# Knight_Rider.net
KiCad netlist of a schematic drawn in EasyEDA Pro
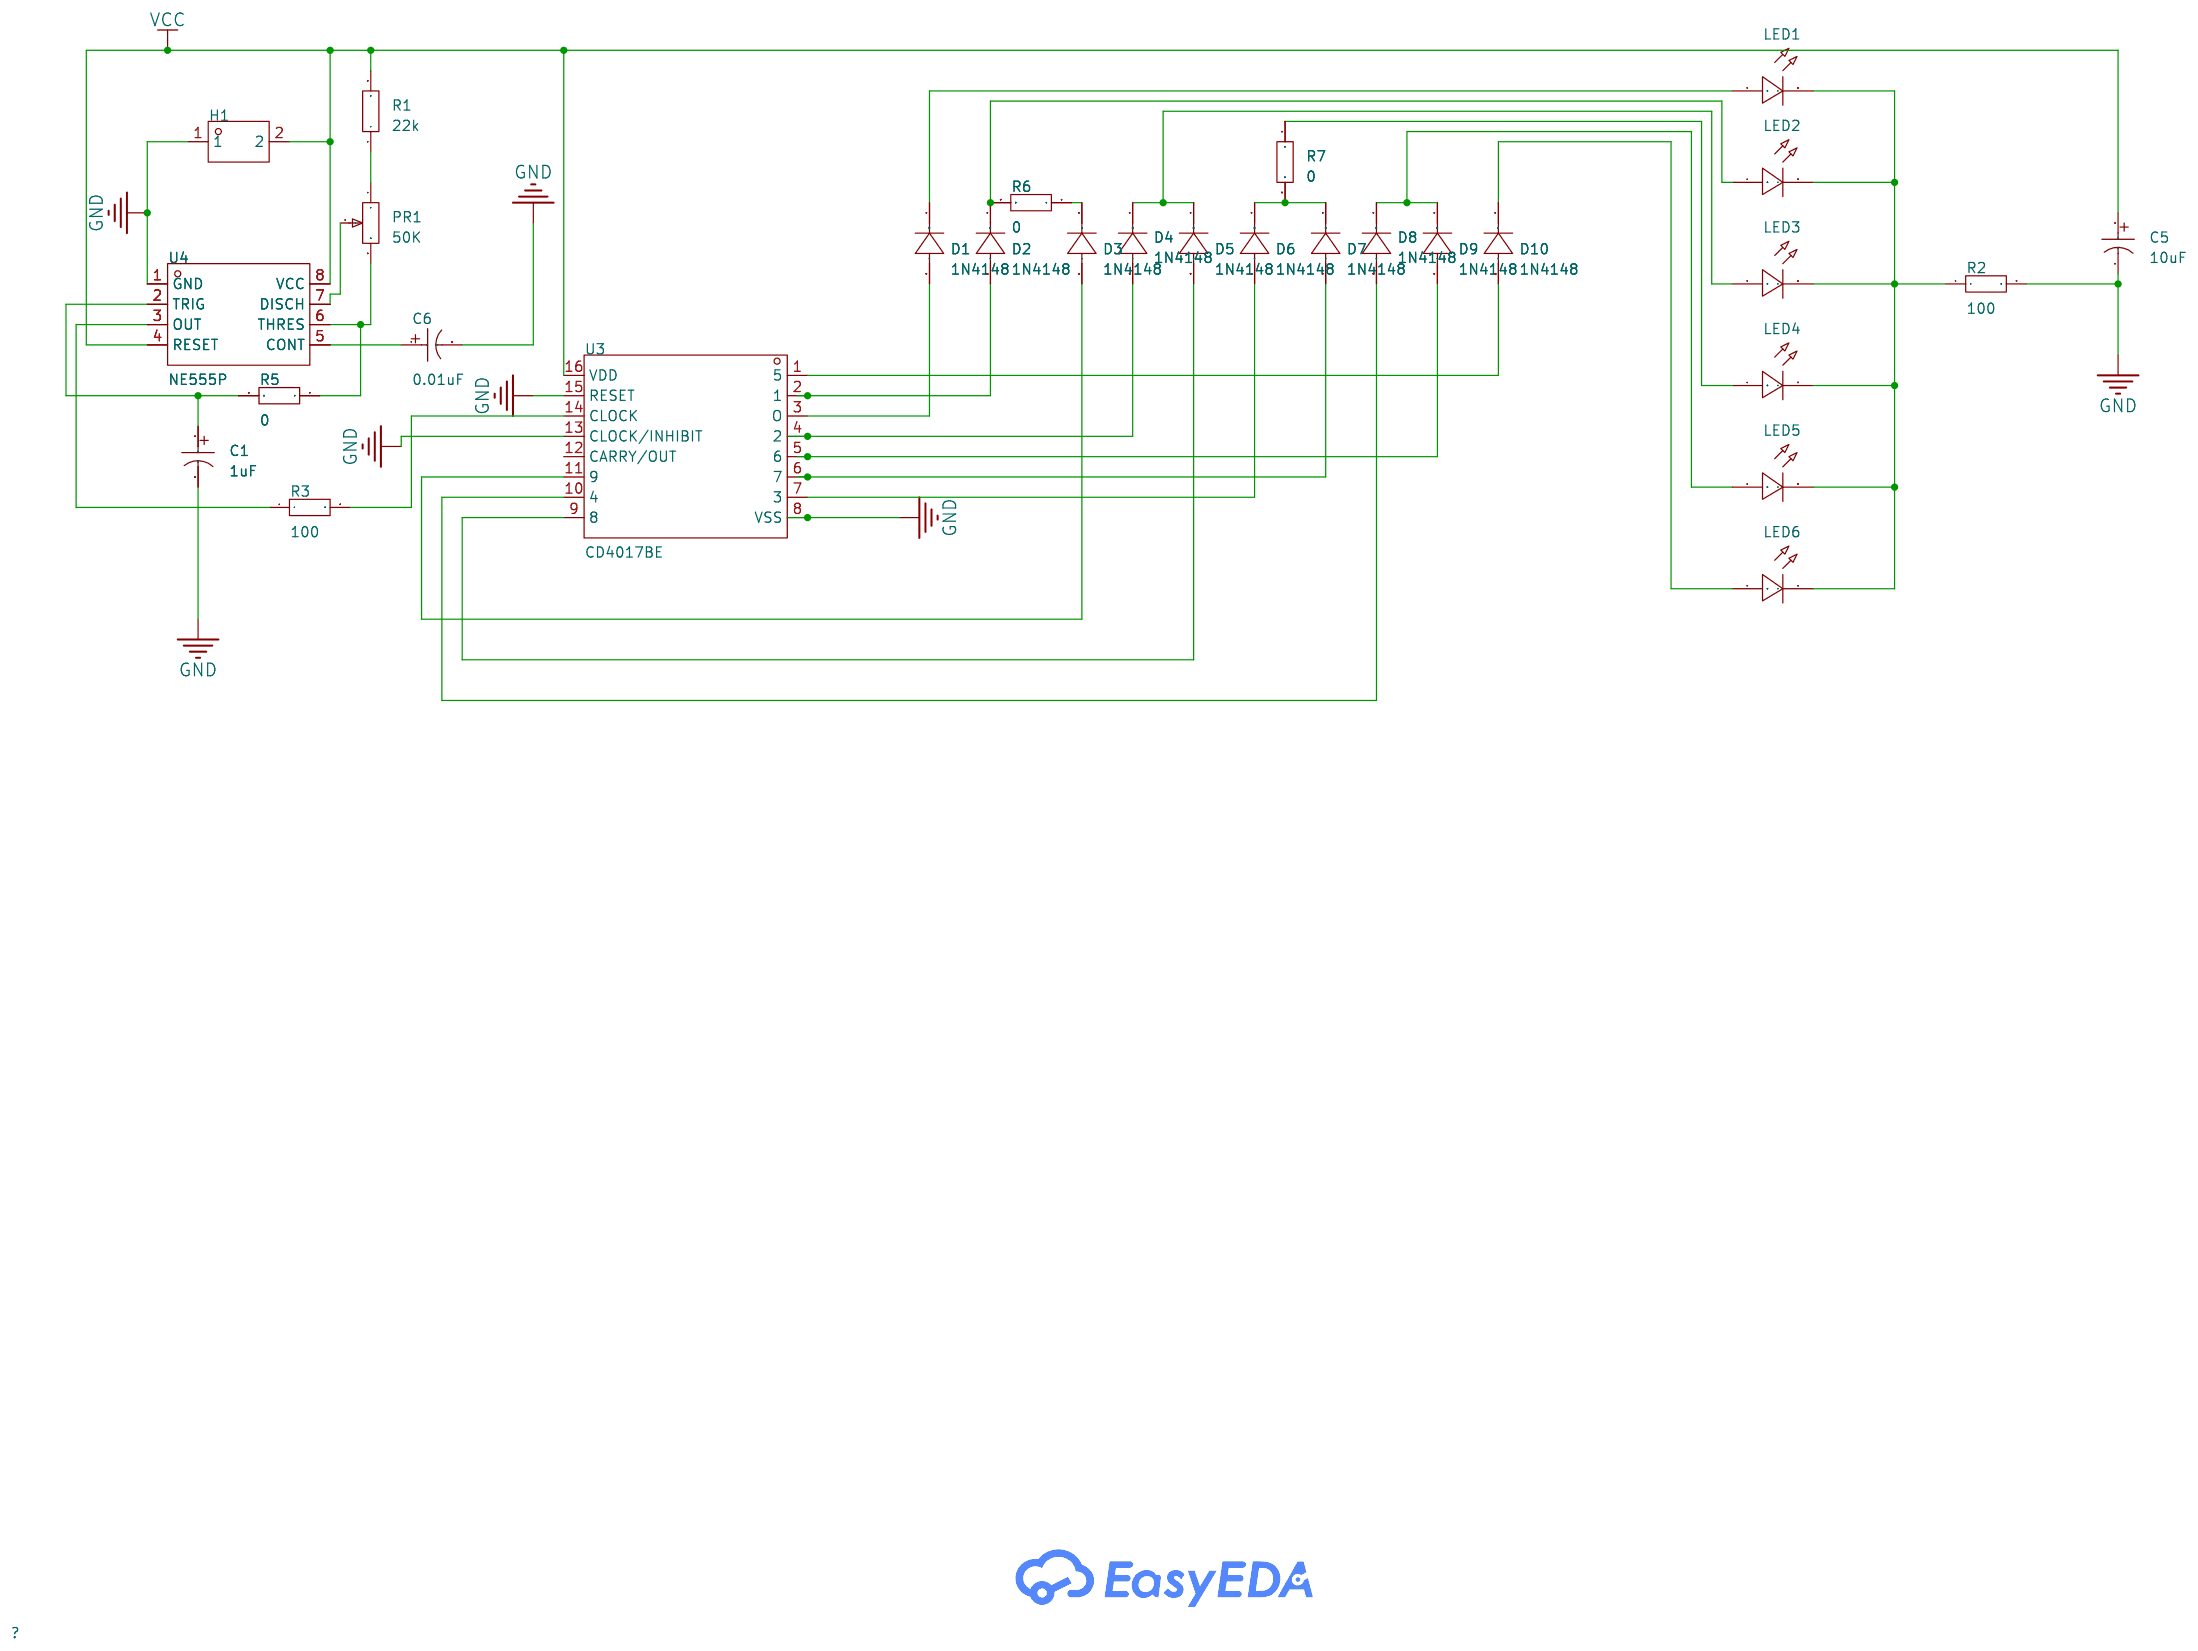
[diagram p0: schematic sheet]

(export (version "E")
  (design (tool "Eeschema 10.0.6"))
  (components
    (comp (ref "C1")
      (value "1uF")
      (footprint "easyedapro:CAP-TH_BD6.3-P2.50-D1.0-FD")
      (fields
        (field (name "Manufacturer Part") "KS227M016E07RR0VH2FP0")
        (field (name "Manufacturer") "Chengx(承兴)")
      )
      (libsource (lib "easyedapro") (part "220uF 16V 6.3*7"))
    )
    (comp (ref "C5")
      (value "10uF")
      (footprint "easyedapro:CAP-TH_BD6.3-P2.50-D1.0-FD")
      (fields
        (field (name "Manufacturer Part") "KS227M016E07RR0VH2FP0")
        (field (name "Manufacturer") "Chengx(承兴)")
      )
      (libsource (lib "easyedapro") (part "220uF 16V 6.3*7"))
    )
    (comp (ref "C6")
      (value "0.01uF")
      (footprint "easyedapro:CAP-TH_BD6.3-P2.50-D1.0-FD")
      (fields
        (field (name "Manufacturer Part") "KS227M016E07RR0VH2FP0")
        (field (name "Manufacturer") "Chengx(承兴)")
      )
      (libsource (lib "easyedapro") (part "220uF 16V 6.3*7"))
    )
    (comp (ref "D1")
      (value "1N4148")
      (footprint "easyedapro:DO-35_BD1.7-L3.6-P10.00-D0.5-RD")
      (fields (field (name "Manufacturer") "DIOTEC(德欧泰克)"))
      (libsource (lib "easyedapro") (part "1N4148_C22434654"))
    )
    (comp (ref "D2")
      (value "1N4148")
      (footprint "easyedapro:DO-35_BD1.7-L3.6-P10.00-D0.5-RD")
      (fields (field (name "Manufacturer") "DIOTEC(德欧泰克)"))
      (libsource (lib "easyedapro") (part "1N4148_C22434654"))
    )
    (comp (ref "D3")
      (value "1N4148")
      (footprint "easyedapro:DO-35_BD1.7-L3.6-P10.00-D0.5-RD")
      (fields (field (name "Manufacturer") "DIOTEC(德欧泰克)"))
      (libsource (lib "easyedapro") (part "1N4148_C22434654"))
    )
    (comp (ref "D4")
      (value "1N4148")
      (footprint "easyedapro:DO-35_BD1.7-L3.6-P10.00-D0.5-RD")
      (fields (field (name "Manufacturer") "DIOTEC(德欧泰克)"))
      (libsource (lib "easyedapro") (part "1N4148_C22434654"))
    )
    (comp (ref "D5")
      (value "1N4148")
      (footprint "easyedapro:DO-35_BD1.7-L3.6-P10.00-D0.5-RD")
      (fields (field (name "Manufacturer") "DIOTEC(德欧泰克)"))
      (libsource (lib "easyedapro") (part "1N4148_C22434654"))
    )
    (comp (ref "D6")
      (value "1N4148")
      (footprint "easyedapro:DO-35_BD1.7-L3.6-P10.00-D0.5-RD")
      (fields (field (name "Manufacturer") "DIOTEC(德欧泰克)"))
      (libsource (lib "easyedapro") (part "1N4148_C22434654"))
    )
    (comp (ref "D7")
      (value "1N4148")
      (footprint "easyedapro:DO-35_BD1.7-L3.6-P10.00-D0.5-RD")
      (fields (field (name "Manufacturer") "DIOTEC(德欧泰克)"))
      (libsource (lib "easyedapro") (part "1N4148_C22434654"))
    )
    (comp (ref "D8")
      (value "1N4148")
      (footprint "easyedapro:DO-35_BD1.7-L3.6-P10.00-D0.5-RD")
      (fields (field (name "Manufacturer") "DIOTEC(德欧泰克)"))
      (libsource (lib "easyedapro") (part "1N4148_C22434654"))
    )
    (comp (ref "D9")
      (value "1N4148")
      (footprint "easyedapro:DO-35_BD1.7-L3.6-P10.00-D0.5-RD")
      (fields (field (name "Manufacturer") "DIOTEC(德欧泰克)"))
      (libsource (lib "easyedapro") (part "1N4148_C22434654"))
    )
    (comp (ref "D10")
      (value "1N4148")
      (footprint "easyedapro:DO-35_BD1.7-L3.6-P10.00-D0.5-RD")
      (fields (field (name "Manufacturer") "DIOTEC(德欧泰克)"))
      (libsource (lib "easyedapro") (part "1N4148_C22434654"))
    )
    (comp (ref "H1")
      (value "~")
      (footprint "easyedapro:HDR-TH_2P-P2.54-V-M-2")
      (libsource (lib "easyedapro") (part "HDR-M-2.54_2x1"))
    )
    (comp (ref "LED1")
      (value "~")
      (footprint "easyedapro:LED-TH_BD3.0-P2.54-FD")
      (libsource (lib "easyedapro") (part "LED_TH-R"))
    )
    (comp (ref "LED2")
      (value "~")
      (footprint "easyedapro:LED-TH_BD3.0-P2.54-FD")
      (libsource (lib "easyedapro") (part "LED_TH-R"))
    )
    (comp (ref "LED3")
      (value "~")
      (footprint "easyedapro:LED-TH_BD3.0-P2.54-FD")
      (libsource (lib "easyedapro") (part "LED_TH-R"))
    )
    (comp (ref "LED4")
      (value "~")
      (footprint "easyedapro:LED-TH_BD3.0-P2.54-FD")
      (libsource (lib "easyedapro") (part "LED_TH-R"))
    )
    (comp (ref "LED5")
      (value "~")
      (footprint "easyedapro:LED-TH_BD3.0-P2.54-FD")
      (libsource (lib "easyedapro") (part "LED_TH-R"))
    )
    (comp (ref "LED6")
      (value "~")
      (footprint "easyedapro:LED-TH_BD3.0-P2.54-FD")
      (libsource (lib "easyedapro") (part "LED_TH-R"))
    )
    (comp (ref "PR1")
      (value "50K")
      (footprint "easyedapro:RES-ADJ-TH_3P-L9.5-W9.5-P2.54-BR-BS")
      (libsource (lib "easyedapro") (part "3386P-1-103LF"))
    )
    (comp (ref "R1")
      (value "22k")
      (footprint "easyedapro:RES-TH_BD1.8-L3.2-P7.20-D0.4")
      (libsource (lib "easyedapro") (part "Res"))
    )
    (comp (ref "R2")
      (value "100")
      (footprint "easyedapro:RES-TH_BD1.8-L3.2-P7.20-D0.4")
      (libsource (lib "easyedapro") (part "Res"))
    )
    (comp (ref "R3")
      (value "100")
      (footprint "easyedapro:RES-TH_BD1.8-L3.2-P7.20-D0.4")
      (libsource (lib "easyedapro") (part "Res"))
    )
    (comp (ref "R5")
      (value "0")
      (footprint "easyedapro:RES-TH_BD1.8-L3.2-P7.20-D0.4")
      (libsource (lib "easyedapro") (part "Res"))
    )
    (comp (ref "R6")
      (value "0")
      (footprint "easyedapro:RES-TH_BD1.8-L3.2-P7.20-D0.4")
      (libsource (lib "easyedapro") (part "Res"))
    )
    (comp (ref "R7")
      (value "0")
      (footprint "easyedapro:RES-TH_BD1.8-L3.2-P7.20-D0.4")
      (libsource (lib "easyedapro") (part "Res"))
    )
    (comp (ref "U3")
      (value "CD4017BE")
      (footprint "easyedapro:DIP-16_16P-L20.2-W6.6-P2.54-LS7.6-BL")
      (fields (field (name "Manufacturer") "TI(德州仪器)"))
      (libsource (lib "easyedapro") (part "CD4017BE"))
    )
    (comp (ref "U4")
      (value "NE555P")
      (footprint "easyedapro:DIP-8_L9.8-W6.6-P2.54-LS7.6-BL")
      (fields (field (name "Manufacturer") "TI(德州仪器)"))
      (libsource (lib "easyedapro") (part "NE555P"))
    )
  )
  (nets
    (net (code "1") (name "GND") (class "Default")
      (node (ref "C1") (pin "2") (pinfunction "2_2") (pintype "input"))
      (node (ref "C5") (pin "2") (pinfunction "2_2") (pintype "input"))
      (node (ref "C6") (pin "2") (pinfunction "2_2") (pintype "input"))
      (node (ref "H1") (pin "1") (pinfunction "1_1") (pintype "input"))
      (node (ref "R2") (pin "2") (pinfunction "2_2") (pintype "input"))
      (node (ref "U3") (pin "13") (pinfunction "CLOCK/INHIBIT_13") (pintype "unspecified"))
      (node (ref "U3") (pin "15") (pinfunction "RESET_15") (pintype "unspecified"))
      (node (ref "U3") (pin "8") (pinfunction "VSS_8") (pintype "unspecified"))
      (node (ref "U4") (pin "1") (pinfunction "GND_1") (pintype "input"))
    )
    (net (code "2") (name "Net-(D1-A)") (class "Default")
      (node (ref "D1") (pin "2") (pinfunction "A_2") (pintype "unspecified"))
      (node (ref "U3") (pin "3") (pinfunction "O_3") (pintype "unspecified"))
    )
    (net (code "3") (name "Net-(D1-C)") (class "Default")
      (node (ref "D1") (pin "1") (pinfunction "C_1") (pintype "unspecified"))
      (node (ref "LED1") (pin "1") (pinfunction "C_1") (pintype "input"))
    )
    (net (code "4") (name "Net-(D2-A)") (class "Default")
      (node (ref "D2") (pin "2") (pinfunction "A_2") (pintype "unspecified"))
      (node (ref "U3") (pin "2") (pinfunction "1_2") (pintype "unspecified"))
    )
    (net (code "5") (name "Net-(D2-C)") (class "Default")
      (node (ref "D2") (pin "1") (pinfunction "C_1") (pintype "unspecified"))
      (node (ref "LED2") (pin "1") (pinfunction "C_1") (pintype "input"))
      (node (ref "R6") (pin "2") (pinfunction "2_2") (pintype "input"))
    )
    (net (code "6") (name "Net-(D3-A)") (class "Default")
      (node (ref "D3") (pin "2") (pinfunction "A_2") (pintype "unspecified"))
      (node (ref "U3") (pin "11") (pinfunction "9_11") (pintype "unspecified"))
    )
    (net (code "7") (name "Net-(D3-C)") (class "Default")
      (node (ref "D3") (pin "1") (pinfunction "C_1") (pintype "unspecified"))
      (node (ref "R6") (pin "1") (pinfunction "1_1") (pintype "input"))
    )
    (net (code "8") (name "Net-(D4-A)") (class "Default")
      (node (ref "D4") (pin "2") (pinfunction "A_2") (pintype "unspecified"))
      (node (ref "U3") (pin "4") (pinfunction "2_4") (pintype "unspecified"))
    )
    (net (code "9") (name "Net-(D4-C)") (class "Default")
      (node (ref "D4") (pin "1") (pinfunction "C_1") (pintype "unspecified"))
      (node (ref "D5") (pin "1") (pinfunction "C_1") (pintype "unspecified"))
      (node (ref "LED3") (pin "1") (pinfunction "C_1") (pintype "input"))
    )
    (net (code "10") (name "Net-(D5-A)") (class "Default")
      (node (ref "D5") (pin "2") (pinfunction "A_2") (pintype "unspecified"))
      (node (ref "U3") (pin "9") (pinfunction "8_9") (pintype "unspecified"))
    )
    (net (code "11") (name "Net-(D6-A)") (class "Default")
      (node (ref "D6") (pin "2") (pinfunction "A_2") (pintype "unspecified"))
      (node (ref "U3") (pin "7") (pinfunction "3_7") (pintype "unspecified"))
    )
    (net (code "12") (name "Net-(D6-C)") (class "Default")
      (node (ref "D6") (pin "1") (pinfunction "C_1") (pintype "unspecified"))
      (node (ref "D7") (pin "1") (pinfunction "C_1") (pintype "unspecified"))
      (node (ref "R7") (pin "2") (pinfunction "2_2") (pintype "input"))
    )
    (net (code "13") (name "Net-(D7-A)") (class "Default")
      (node (ref "D7") (pin "2") (pinfunction "A_2") (pintype "unspecified"))
      (node (ref "U3") (pin "6") (pinfunction "7_6") (pintype "unspecified"))
    )
    (net (code "14") (name "Net-(D8-A)") (class "Default")
      (node (ref "D8") (pin "2") (pinfunction "A_2") (pintype "unspecified"))
      (node (ref "U3") (pin "10") (pinfunction "4_10") (pintype "unspecified"))
    )
    (net (code "15") (name "Net-(D8-C)") (class "Default")
      (node (ref "D8") (pin "1") (pinfunction "C_1") (pintype "unspecified"))
      (node (ref "D9") (pin "1") (pinfunction "C_1") (pintype "unspecified"))
      (node (ref "LED5") (pin "1") (pinfunction "C_1") (pintype "input"))
    )
    (net (code "16") (name "Net-(D9-A)") (class "Default")
      (node (ref "D9") (pin "2") (pinfunction "A_2") (pintype "unspecified"))
      (node (ref "U3") (pin "5") (pinfunction "6_5") (pintype "unspecified"))
    )
    (net (code "17") (name "Net-(D10-A)") (class "Default")
      (node (ref "D10") (pin "2") (pinfunction "A_2") (pintype "unspecified"))
      (node (ref "U3") (pin "1") (pinfunction "5_1") (pintype "unspecified"))
    )
    (net (code "18") (name "Net-(D10-C)") (class "Default")
      (node (ref "D10") (pin "1") (pinfunction "C_1") (pintype "unspecified"))
      (node (ref "LED6") (pin "1") (pinfunction "C_1") (pintype "input"))
    )
    (net (code "19") (name "Net-(LED1-A)") (class "Default")
      (node (ref "LED1") (pin "2") (pinfunction "A_2") (pintype "input"))
      (node (ref "LED2") (pin "2") (pinfunction "A_2") (pintype "input"))
      (node (ref "LED3") (pin "2") (pinfunction "A_2") (pintype "input"))
      (node (ref "LED4") (pin "2") (pinfunction "A_2") (pintype "input"))
      (node (ref "LED5") (pin "2") (pinfunction "A_2") (pintype "input"))
      (node (ref "LED6") (pin "2") (pinfunction "A_2") (pintype "input"))
      (node (ref "R2") (pin "1") (pinfunction "1_1") (pintype "input"))
    )
    (net (code "20") (name "Net-(LED4-C)") (class "Default")
      (node (ref "LED4") (pin "1") (pinfunction "C_1") (pintype "input"))
      (node (ref "R7") (pin "1") (pinfunction "1_1") (pintype "input"))
    )
    (net (code "21") (name "Net-(PR1-Pad1)") (class "Default")
      (node (ref "PR1") (pin "1") (pinfunction "1_1") (pintype "input"))
      (node (ref "R1") (pin "1") (pinfunction "1_1") (pintype "input"))
    )
    (net (code "22") (name "Net-(U3-CLOCK)") (class "Default")
      (node (ref "R3") (pin "2") (pinfunction "2_2") (pintype "input"))
      (node (ref "U3") (pin "14") (pinfunction "CLOCK_14") (pintype "unspecified"))
    )
    (net (code "23") (name "Net-(U4-CONT)") (class "Default")
      (node (ref "C6") (pin "1") (pinfunction "1_1") (pintype "input"))
      (node (ref "U4") (pin "5") (pinfunction "CONT_5") (pintype "input"))
    )
    (net (code "24") (name "Net-(U4-DISCH)") (class "Default")
      (node (ref "PR1") (pin "2") (pinfunction "2_2") (pintype "input"))
      (node (ref "U4") (pin "7") (pinfunction "DISCH_7") (pintype "input"))
    )
    (net (code "25") (name "Net-(U4-OUT)") (class "Default")
      (node (ref "R3") (pin "1") (pinfunction "1_1") (pintype "input"))
      (node (ref "U4") (pin "3") (pinfunction "OUT_3") (pintype "input"))
    )
    (net (code "26") (name "Net-(U4-THRES)") (class "Default")
      (node (ref "PR1") (pin "3") (pinfunction "3_3") (pintype "input"))
      (node (ref "R5") (pin "1") (pinfunction "1_1") (pintype "input"))
      (node (ref "U4") (pin "6") (pinfunction "THRES_6") (pintype "input"))
    )
    (net (code "27") (name "Net-(U4-TRIG)") (class "Default")
      (node (ref "C1") (pin "1") (pinfunction "1_1") (pintype "input"))
      (node (ref "R5") (pin "2") (pinfunction "2_2") (pintype "input"))
      (node (ref "U4") (pin "2") (pinfunction "TRIG_2") (pintype "input"))
    )
    (net (code "28") (name "VCC") (class "Default")
      (node (ref "C5") (pin "1") (pinfunction "1_1") (pintype "input"))
      (node (ref "H1") (pin "2") (pinfunction "2_2") (pintype "input"))
      (node (ref "R1") (pin "2") (pinfunction "2_2") (pintype "input"))
      (node (ref "U3") (pin "16") (pinfunction "VDD_16") (pintype "unspecified"))
      (node (ref "U4") (pin "4") (pinfunction "RESET_4") (pintype "input"))
      (node (ref "U4") (pin "8") (pinfunction "VCC_8") (pintype "input"))
    )
    (net (code "29") (name "unconnected-(U3-CARRY{slash}OUT-Pad12)") (class "Default")
      (node (ref "U3") (pin "12") (pinfunction "CARRY/OUT_12") (pintype "unspecified"))
    )
  )
)
